# Temperature_Sensor.net
KiCad netlist of a schematic drawn in Altium Designer
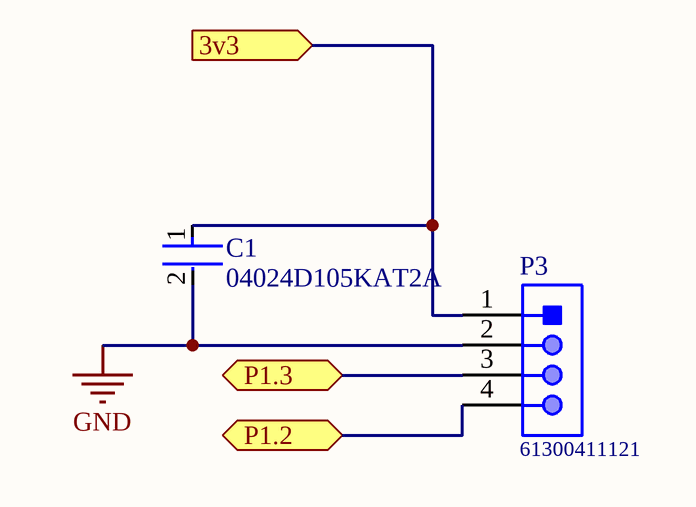
[diagram p0: Temperature Sensor.SchDoc]

(export (version "E")
  (design (tool "Eeschema 10.0.6"))
  (components
    (comp (ref "C1")
      (value "04024D105KAT2A")
      (footprint "FP-0402-L_1_0_1-W_0_5_0_1-MFG")
      (description "General Purpose Ceramic Capacitor, 0402, 1uF, 10%, X5R, 15%, 4V")
      (fields (field (name "TOLERANCE") "10%"))
      (libsource (lib "Altium Content Vault") (part "b4654b650e69147ec39a6b967a45e02"))
    )
    (comp (ref "P3")
      (value "61300411121")
      (footprint "61300411121")
      (description "THT Vertical Pin Header WR-PHD, Pitch 2.54 mm, Single Row, 4 pins")
      (fields (field (name "MANUFACTURER") "Wurth Elektronik") (field (name "PUBLISHER") "WurthElektronik"))
      (libsource (lib "Altium Content Vault") (part "WE-CN-1P-M-R4"))
    )
  )
  (nets
    (net (code "1") (name "/3v3") (class "Default")
      (node (ref "C1") (pin "1") (pinfunction "1_1") (pintype "passive"))
      (node (ref "P3") (pin "1") (pinfunction "1_1") (pintype "passive"))
    )
    (net (code "2") (name "/P1.2") (class "Default")
      (node (ref "P3") (pin "4") (pinfunction "4_4") (pintype "passive"))
    )
    (net (code "3") (name "/P1.3") (class "Default")
      (node (ref "P3") (pin "3") (pinfunction "3_3") (pintype "passive"))
    )
    (net (code "4") (name "GND") (class "Default")
      (node (ref "C1") (pin "2") (pinfunction "2_2") (pintype "passive"))
      (node (ref "P3") (pin "2") (pinfunction "2_2") (pintype "passive"))
    )
  )
)
